# NJM2396.net
KiCad netlist of a schematic drawn in EAGLE
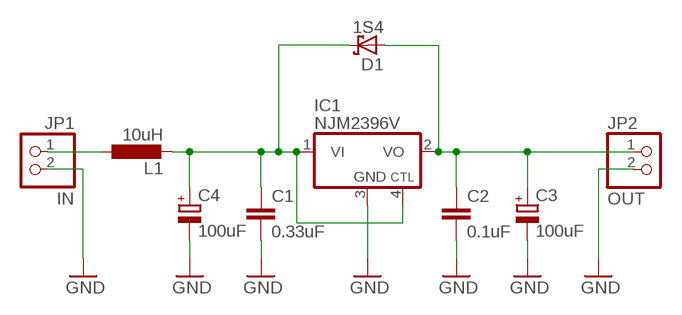
[diagram p0: schematic, sheet 1]

(export (version "E")
  (design (tool "Eeschema 10.0.6"))
  (components
    (comp (ref "C1")
      (value "0.33uF")
      (footprint "eagle-import:C050-030X075")
      (libsource (lib "eagle-import") (part "C-EU050-030X075"))
    )
    (comp (ref "C2")
      (value "0.1uF")
      (footprint "eagle-import:C025-024X044")
      (libsource (lib "eagle-import") (part "C-EU025-024X044"))
    )
    (comp (ref "C3")
      (value "100uF")
      (footprint "eagle-import:SANYO-OSCON_E13")
      (libsource (lib "eagle-import") (part "CPOL-EUSANYO_E13"))
    )
    (comp (ref "C4")
      (value "100uF")
      (footprint "eagle-import:SANYO-OSCON_E13")
      (libsource (lib "eagle-import") (part "CPOL-EUSANYO_E13"))
    )
    (comp (ref "D1")
      (value "1S4")
      (footprint "eagle-import:DO35-7")
      (libsource (lib "eagle-import") (part "SCHOTTKY-DIODEDO35-7"))
    )
    (comp (ref "IC1")
      (value "NJM2396V")
      (footprint "eagle-import:TO220-4V")
      (libsource (lib "eagle-import") (part "NJM2396V"))
    )
    (comp (ref "JP1")
      (value "IN")
      (footprint "eagle-import:1X02")
      (libsource (lib "eagle-import") (part "PINHD-1X2"))
    )
    (comp (ref "JP2")
      (value "OUT")
      (footprint "eagle-import:1X02")
      (libsource (lib "eagle-import") (part "PINHD-1X2"))
    )
    (comp (ref "L1")
      (value "10uH")
      (footprint "eagle-import:6000-XXXX-RC")
      (libsource (lib "eagle-import") (part "L-EU6000-XXX-RC"))
    )
  )
  (nets
    (net (code "1") (name "GND") (class "Default")
      (node (ref "C1") (pin "2") (pinfunction "2_2") (pintype "passive"))
      (node (ref "C2") (pin "2") (pinfunction "2_2") (pintype "passive"))
      (node (ref "C3") (pin "-") (pinfunction "-_-") (pintype "passive"))
      (node (ref "C4") (pin "-") (pinfunction "-_-") (pintype "passive"))
      (node (ref "IC1") (pin "3") (pinfunction "GND_3") (pintype "power_in"))
      (node (ref "JP1") (pin "2") (pinfunction "2_2") (pintype "passive"))
      (node (ref "JP2") (pin "2") (pinfunction "2_2") (pintype "passive"))
    )
    (net (code "2") (name "Net-(IC1-CTL)") (class "Default")
      (node (ref "C1") (pin "1") (pinfunction "1_1") (pintype "passive"))
      (node (ref "C4") (pin "+") (pinfunction "+_+") (pintype "passive"))
      (node (ref "D1") (pin "C") (pinfunction "C_C") (pintype "passive"))
      (node (ref "IC1") (pin "1") (pinfunction "VI_1") (pintype "input"))
      (node (ref "IC1") (pin "4") (pinfunction "CTL_4") (pintype "input"))
      (node (ref "L1") (pin "2") (pinfunction "2_2") (pintype "passive"))
    )
    (net (code "3") (name "Net-(IC1-VO)") (class "Default")
      (node (ref "C2") (pin "1") (pinfunction "1_1") (pintype "passive"))
      (node (ref "C3") (pin "+") (pinfunction "+_+") (pintype "passive"))
      (node (ref "D1") (pin "A") (pinfunction "A_A") (pintype "passive"))
      (node (ref "IC1") (pin "2") (pinfunction "VO_2") (pintype "output"))
      (node (ref "JP2") (pin "1") (pinfunction "1_1") (pintype "passive"))
    )
    (net (code "4") (name "Net-(JP1-Pad1)") (class "Default")
      (node (ref "JP1") (pin "1") (pinfunction "1_1") (pintype "passive"))
      (node (ref "L1") (pin "1") (pinfunction "1_1") (pintype "passive"))
    )
  )
)
